# Esquematico_TSAL_controladora.net
KiCad netlist of a schematic drawn in Altium Designer
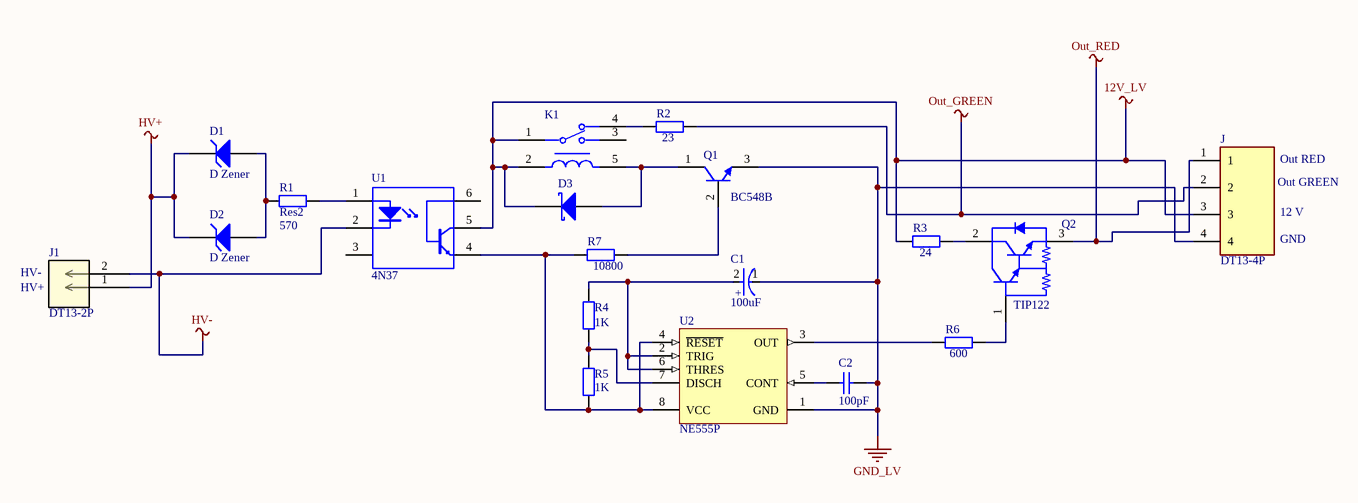
[diagram p0: Esquematico_TSAL_controladora.SchDoc]

(export (version "E")
  (design (tool "Eeschema 10.0.6"))
  (components
    (comp (ref "C1")
      (value "UKL1A101KED1TD")
      (footprint "FP-UKL1A101KED1TD-MFG")
      (description "CAP ALUM 100UF 10% 10V RADIAL")
      (fields
        (field (name "TOLERANCE") "10%")
        (field (name "MANUFACTURER") "Nichicon")
        (field (name "CAPACITANCE") "100uF")
      )
      (libsource (lib "Altium Content Vault") (part "203bc49f2ac43e59fd269a8c329ed05"))
    )
    (comp (ref "C2")
      (value "100pF")
      (footprint "RAD-0.3")
      (description "Capacitor")
      (fields (field (name "Comment") "Cap") (field (name "PUBLISHER") "Altium Limited"))
      (libsource (lib "Miscellaneous Devices") (part "Cap"))
    )
    (comp (ref "D1")
      (value "D Zener")
      (footprint "DIODE-0.7")
      (description "Zener Diode")
      (fields (field (name "PUBLISHER") "Altium Limited"))
      (libsource (lib "Miscellaneous Devices") (part "D Zener"))
    )
    (comp (ref "D2")
      (value "D Zener")
      (footprint "DIODE-0.7")
      (description "Zener Diode")
      (fields (field (name "PUBLISHER") "Altium Limited"))
      (libsource (lib "Miscellaneous Devices") (part "D Zener"))
    )
    (comp (ref "D3")
      (value "Diode 10TQ035")
      (footprint "TO-220AC")
      (description "Schottky Rectifier")
      (fields (field (name "PUBLISHER") "Altium Limited"))
      (libsource (lib "Miscellaneous Devices") (part "Diode 10TQ035"))
    )
    (comp (ref "J")
      (value "DT13-4P")
      (footprint "TE_DT13-4P")
      (description "DT13 Series, 4.44mm Pitch 4 Way 2 Row Right Angle PCB Header, Solder Termination")
      (fields (field (name "MF") "TE Connectivity"))
      (libsource (lib "DT13-4P") (part "DT13-4P"))
    )
    (comp (ref "J1")
      (value "DT13-2P")
      (footprint "CONN2_DT13-2P_TEC")
      (description "No Description Available")
      (libsource (lib "DT13-2P") (part "DT13-2P"))
    )
    (comp (ref "K1")
      (value "G5LE-14-CF-36 DC12")
      (footprint "FP-G5LE-14-CF-36_DC12-MFG")
      (description "RELAY GEN PURPOSE")
      (libsource (lib "Altium Content Vault") (part "2ce9b9867cfa6d2d673578092c768ea"))
    )
    (comp (ref "Q1")
      (value "BC548B")
      (footprint "ONSC-TO-92-3-29-11")
      (description "Amplifier Transistor, NPN Silicon, 3-Pin TO-92, Bulk Box")
      (fields (field (name "MANUFACTURER") "On Semiconductor"))
      (libsource (lib "Altium Content Vault") (part "ONSC-NPN-C1B2E3-3"))
    )
    (comp (ref "Q2")
      (value "TIP122")
      (footprint "ONSC-TO-220-3-221A-09")
      (description "Plastic Medium-Power, Complementary Silicon Transistor, 3-Pin TO-220, Tube")
      (fields (field (name "MANUFACTURER") "On Semiconductor"))
      (libsource (lib "Altium Content Vault") (part "ONSC-DT-NPN-B1C2E3-3_A"))
    )
    (comp (ref "R1")
      (value "Res2")
      (footprint "AXIAL-0.4")
      (description "Resistor")
      (fields (field (name "ALTIUM_VALUE") "570") (field (name "PUBLISHER") "Altium Limited"))
      (libsource (lib "Miscellaneous Devices") (part "Res2"))
    )
    (comp (ref "R2")
      (value "23")
      (footprint "AXIAL-0.4")
      (description "Resistor")
      (fields (field (name "Comment") "Res2") (field (name "PUBLISHER") "Altium Limited"))
      (libsource (lib "Miscellaneous Devices") (part "Res2"))
    )
    (comp (ref "R3")
      (value "24")
      (footprint "AXIAL-0.4")
      (description "Resistor")
      (fields (field (name "Comment") "Res2") (field (name "PUBLISHER") "Altium Limited"))
      (libsource (lib "Miscellaneous Devices") (part "Res2"))
    )
    (comp (ref "R4")
      (value "1K")
      (footprint "AXIAL-0.4")
      (description "Resistor")
      (fields (field (name "Comment") "Res2") (field (name "PUBLISHER") "Altium Limited"))
      (libsource (lib "") (part "Res2_1"))
    )
    (comp (ref "R5")
      (value "1K")
      (footprint "AXIAL-0.4")
      (description "Resistor")
      (fields (field (name "Comment") "Res2") (field (name "PUBLISHER") "Altium Limited"))
      (libsource (lib "") (part "Res2_1"))
    )
    (comp (ref "R6")
      (value "600")
      (footprint "AXIAL-0.4")
      (description "Resistor")
      (fields (field (name "Comment") "Res2") (field (name "PUBLISHER") "Altium Limited"))
      (libsource (lib "Miscellaneous Devices") (part "Res2"))
    )
    (comp (ref "R7")
      (value "10800")
      (footprint "AXIAL-0.4")
      (description "Resistor")
      (fields (field (name "Comment") "Res2") (field (name "PUBLISHER") "Altium Limited"))
      (libsource (lib "Miscellaneous Devices") (part "Res2"))
    )
    (comp (ref "U1")
      (value "4N37")
      (footprint "LTST-DIP-6_A")
      (description "Photocoupler - Phototransistor Output, 1500 Vrms, -55 to 100 degC, 6-Pin DIP, RoHS, Tube")
      (fields (field (name "MANUFACTURER") "Vishay"))
      (libsource (lib "Altium Content Vault") (part "OPTO-AKNECB-6"))
    )
    (comp (ref "U2")
      (value "NE555P")
      (footprint "P0008A")
      (description "Precision Timer, 4.5 to 16 V, 0 to 70 degC, 8-Pin DIP, Pb-Free, Tube")
      (fields (field (name "MANUFACTURER") "TexasInstruments"))
      (libsource (lib "Altium Content Vault") (part "TI-NE555-P8"))
    )
  )
  (nets
    (net (code "1") (name "12V_LV") (class "Default")
      (node (ref "D3") (pin "1") (pinfunction "K_1") (pintype "passive"))
      (node (ref "J") (pin "3") (pinfunction "3_3") (pintype "passive"))
      (node (ref "K1") (pin "1") (pinfunction "1_1") (pintype "passive"))
      (node (ref "K1") (pin "2") (pinfunction "2_2") (pintype "passive"))
      (node (ref "R3") (pin "1") (pinfunction "1_1") (pintype "passive"))
      (node (ref "U1") (pin "5") (pinfunction "C_5") (pintype "passive"))
    )
    (net (code "2") (name "GND_LV") (class "Default")
      (node (ref "C1") (pin "1") (pinfunction "C_1") (pintype "passive"))
      (node (ref "C2") (pin "2") (pinfunction "2_2") (pintype "passive"))
      (node (ref "J") (pin "4") (pinfunction "4_4") (pintype "passive"))
      (node (ref "Q1") (pin "3") (pinfunction "E_3") (pintype "passive"))
      (node (ref "U2") (pin "1") (pinfunction "GND_1") (pintype "power_in"))
    )
    (net (code "3") (name "HV+") (class "Default")
      (node (ref "D1") (pin "2") (pinfunction "K_2") (pintype "passive"))
      (node (ref "D2") (pin "2") (pinfunction "K_2") (pintype "passive"))
      (node (ref "J1") (pin "1") (pinfunction "1_1") (pintype "passive"))
    )
    (net (code "4") (name "HV-") (class "Default")
      (node (ref "J1") (pin "2") (pinfunction "2_2") (pintype "passive"))
      (node (ref "U1") (pin "2") (pinfunction "C_2") (pintype "passive"))
    )
    (net (code "5") (name "Net-(C1-A)") (class "Default")
      (node (ref "C1") (pin "2") (pinfunction "A_2") (pintype "passive"))
      (node (ref "R4") (pin "2") (pinfunction "2_2") (pintype "passive"))
      (node (ref "U2") (pin "2") (pinfunction "TRIG_2") (pintype "input"))
      (node (ref "U2") (pin "6") (pinfunction "THRES_6") (pintype "input"))
    )
    (net (code "6") (name "Net-(D1-A)") (class "Default")
      (node (ref "D1") (pin "1") (pinfunction "A_1") (pintype "passive"))
      (node (ref "D2") (pin "1") (pinfunction "A_1") (pintype "passive"))
      (node (ref "R1") (pin "1") (pinfunction "1_1") (pintype "passive"))
    )
    (net (code "7") (name "Net-(D3-A)") (class "Default")
      (node (ref "D3") (pin "3") (pinfunction "A_3") (pintype "passive"))
      (node (ref "K1") (pin "5") (pinfunction "5_5") (pintype "passive"))
      (node (ref "Q1") (pin "1") (pinfunction "C_1") (pintype "passive"))
    )
    (net (code "8") (name "Net-(K1-Pad4)") (class "Default")
      (node (ref "K1") (pin "4") (pinfunction "4_4") (pintype "passive"))
      (node (ref "R2") (pin "1") (pinfunction "1_1") (pintype "passive"))
    )
    (net (code "9") (name "Net-(Q1-B)") (class "Default")
      (node (ref "Q1") (pin "2") (pinfunction "B_2") (pintype "passive"))
      (node (ref "R7") (pin "2") (pinfunction "2_2") (pintype "passive"))
    )
    (net (code "10") (name "Net-(Q2-B)") (class "Default")
      (node (ref "Q2") (pin "1") (pinfunction "B_1") (pintype "passive"))
      (node (ref "R6") (pin "2") (pinfunction "2_2") (pintype "passive"))
    )
    (net (code "11") (name "Net-(Q2-C)") (class "Default")
      (node (ref "Q2") (pin "2") (pinfunction "C_2") (pintype "passive"))
      (node (ref "R3") (pin "2") (pinfunction "2_2") (pintype "passive"))
    )
    (net (code "12") (name "Net-(U1-A)") (class "Default")
      (node (ref "R1") (pin "2") (pinfunction "2_2") (pintype "passive"))
      (node (ref "U1") (pin "1") (pinfunction "A_1") (pintype "passive"))
    )
    (net (code "13") (name "Net-(U1-E)") (class "Default")
      (node (ref "R5") (pin "1") (pinfunction "1_1") (pintype "passive"))
      (node (ref "R7") (pin "1") (pinfunction "1_1") (pintype "passive"))
      (node (ref "U1") (pin "4") (pinfunction "E_4") (pintype "passive"))
      (node (ref "U2") (pin "4") (pinfunction "~{RESET}_4") (pintype "input"))
      (node (ref "U2") (pin "8") (pinfunction "VCC_8") (pintype "power_in"))
    )
    (net (code "14") (name "Net-(U2-CONT)") (class "Default")
      (node (ref "C2") (pin "1") (pinfunction "1_1") (pintype "passive"))
      (node (ref "U2") (pin "5") (pinfunction "CONT_5") (pintype "input"))
    )
    (net (code "15") (name "Net-(U2-DISCH)") (class "Default")
      (node (ref "R4") (pin "1") (pinfunction "1_1") (pintype "passive"))
      (node (ref "R5") (pin "2") (pinfunction "2_2") (pintype "passive"))
      (node (ref "U2") (pin "7") (pinfunction "DISCH_7") (pintype "open_collector"))
    )
    (net (code "16") (name "Net-(U2-OUT)") (class "Default")
      (node (ref "R6") (pin "1") (pinfunction "1_1") (pintype "passive"))
      (node (ref "U2") (pin "3") (pinfunction "OUT_3") (pintype "output"))
    )
    (net (code "17") (name "Out_GREEN") (class "Default")
      (node (ref "J") (pin "2") (pinfunction "2_2") (pintype "passive"))
      (node (ref "R2") (pin "2") (pinfunction "2_2") (pintype "passive"))
    )
    (net (code "18") (name "Out_RED") (class "Default")
      (node (ref "J") (pin "1") (pinfunction "1_1") (pintype "passive"))
      (node (ref "Q2") (pin "3") (pinfunction "E_3") (pintype "passive"))
    )
    (net (code "19") (name "unconnected-(K1-Pad3)") (class "Default")
      (node (ref "K1") (pin "3") (pinfunction "3_3") (pintype "passive"))
    )
    (net (code "20") (name "unconnected-(U1-B-Pad6)") (class "Default")
      (node (ref "U1") (pin "6") (pinfunction "B_6") (pintype "passive"))
    )
    (net (code "21") (name "unconnected-(U1-NC-Pad3)") (class "Default")
      (node (ref "U1") (pin "3") (pinfunction "NC_3") (pintype "passive"))
    )
  )
)
